# Sheet1.net
KiCad netlist of a schematic drawn in Altium Designer
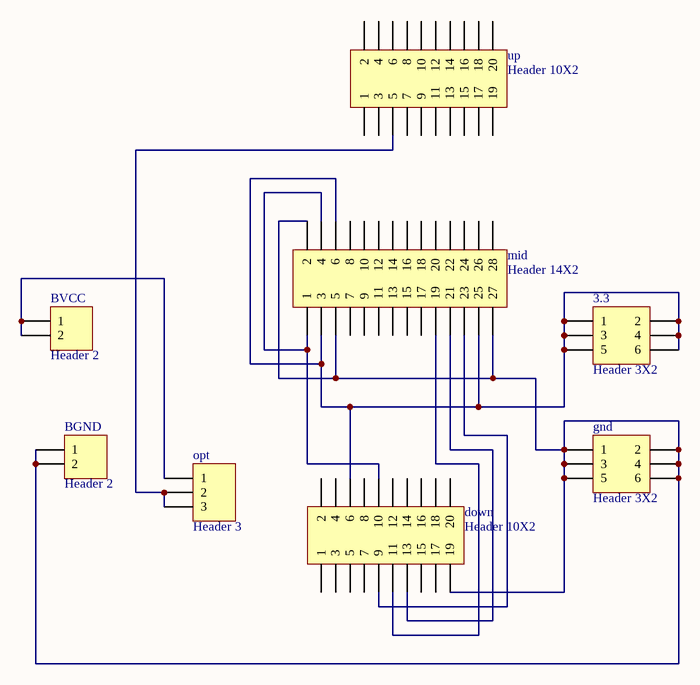
[diagram p0: Sheet1.SchDoc]

(export (version "E")
  (design (tool "Eeschema 10.0.6"))
  (components
    (comp (ref "3.3")
      (value "Header 3X2")
      (footprint "HDR2X3")
      (description "Header, 3-Pin, Dual row")
      (fields (field (name "PUBLISHER") "Altium Limited"))
      (libsource (lib "Miscellaneous Connectors") (part "Header 3X2"))
    )
    (comp (ref "BGND")
      (value "Header 2")
      (footprint "HDR1X2")
      (description "Header, 2-Pin")
      (fields (field (name "PUBLISHER") "Altium Limited"))
      (libsource (lib "Miscellaneous Connectors") (part "Header 2"))
    )
    (comp (ref "BVCC")
      (value "Header 2")
      (footprint "HDR1X2")
      (description "Header, 2-Pin")
      (fields (field (name "PUBLISHER") "Altium Limited"))
      (libsource (lib "Miscellaneous Connectors") (part "Header 2"))
    )
    (comp (ref "down")
      (value "Header 10X2")
      (footprint "HDR2X10")
      (description "Header, 10-Pin, Dual row")
      (fields (field (name "PUBLISHER") "Altium Limited"))
      (libsource (lib "Miscellaneous Connectors") (part "Header 10X2"))
    )
    (comp (ref "gnd")
      (value "Header 3X2")
      (footprint "HDR2X3")
      (description "Header, 3-Pin, Dual row")
      (fields (field (name "PUBLISHER") "Altium Limited"))
      (libsource (lib "Miscellaneous Connectors") (part "Header 3X2"))
    )
    (comp (ref "mid")
      (value "Header 14X2")
      (footprint "HDR2X14")
      (description "Header, 14-Pin, Dual row")
      (fields (field (name "PUBLISHER") "Altium Limited"))
      (libsource (lib "Miscellaneous Connectors") (part "Header 14X2"))
    )
    (comp (ref "opt")
      (value "Header 3")
      (footprint "HDR1X3")
      (description "Header, 3-Pin")
      (fields (field (name "PUBLISHER") "Altium Limited"))
      (libsource (lib "Miscellaneous Connectors") (part "Header 3"))
    )
    (comp (ref "up")
      (value "Header 10X2")
      (footprint "HDR2X10")
      (description "Header, 10-Pin, Dual row")
      (fields (field (name "PUBLISHER") "Altium Limited"))
      (libsource (lib "Miscellaneous Connectors") (part "Header 10X2"))
    )
  )
  (nets
    (net (code "1") (name "Net-(3.3-Pad1)") (class "Default")
      (node (ref "3.3") (pin "1") (pinfunction "1_1") (pintype "passive"))
      (node (ref "3.3") (pin "2") (pinfunction "2_2") (pintype "passive"))
      (node (ref "3.3") (pin "3") (pinfunction "3_3") (pintype "passive"))
      (node (ref "3.3") (pin "4") (pinfunction "4_4") (pintype "passive"))
      (node (ref "3.3") (pin "5") (pinfunction "5_5") (pintype "passive"))
      (node (ref "3.3") (pin "6") (pinfunction "6_6") (pintype "passive"))
      (node (ref "down") (pin "6") (pinfunction "6_6") (pintype "passive"))
      (node (ref "mid") (pin "25") (pinfunction "25_25") (pintype "passive"))
      (node (ref "mid") (pin "3") (pinfunction "3_3") (pintype "passive"))
      (node (ref "mid") (pin "6") (pinfunction "6_6") (pintype "passive"))
    )
    (net (code "2") (name "Net-(BGND-Pad1)") (class "Default")
      (node (ref "BGND") (pin "1") (pinfunction "1_1") (pintype "passive"))
      (node (ref "BGND") (pin "2") (pinfunction "2_2") (pintype "passive"))
      (node (ref "down") (pin "19") (pinfunction "19_19") (pintype "passive"))
      (node (ref "gnd") (pin "1") (pinfunction "1_1") (pintype "passive"))
      (node (ref "gnd") (pin "2") (pinfunction "2_2") (pintype "passive"))
      (node (ref "gnd") (pin "3") (pinfunction "3_3") (pintype "passive"))
      (node (ref "gnd") (pin "4") (pinfunction "4_4") (pintype "passive"))
      (node (ref "gnd") (pin "5") (pinfunction "5_5") (pintype "passive"))
      (node (ref "gnd") (pin "6") (pinfunction "6_6") (pintype "passive"))
      (node (ref "mid") (pin "2") (pinfunction "2_2") (pintype "passive"))
      (node (ref "mid") (pin "27") (pinfunction "27_27") (pintype "passive"))
      (node (ref "mid") (pin "5") (pinfunction "5_5") (pintype "passive"))
    )
    (net (code "3") (name "Net-(BVCC-Pad1)") (class "Default")
      (node (ref "BVCC") (pin "1") (pinfunction "1_1") (pintype "passive"))
      (node (ref "BVCC") (pin "2") (pinfunction "2_2") (pintype "passive"))
      (node (ref "opt") (pin "1") (pinfunction "1_1") (pintype "passive"))
    )
    (net (code "4") (name "Net-(down-Pad9)") (class "Default")
      (node (ref "down") (pin "9") (pinfunction "9_9") (pintype "passive"))
      (node (ref "mid") (pin "23") (pinfunction "23_23") (pintype "passive"))
    )
    (net (code "5") (name "Net-(down-Pad10)") (class "Default")
      (node (ref "down") (pin "10") (pinfunction "10_10") (pintype "passive"))
      (node (ref "mid") (pin "1") (pinfunction "1_1") (pintype "passive"))
      (node (ref "mid") (pin "4") (pinfunction "4_4") (pintype "passive"))
    )
    (net (code "6") (name "Net-(down-Pad11)") (class "Default")
      (node (ref "down") (pin "11") (pinfunction "11_11") (pintype "passive"))
      (node (ref "mid") (pin "19") (pinfunction "19_19") (pintype "passive"))
    )
    (net (code "7") (name "Net-(down-Pad13)") (class "Default")
      (node (ref "down") (pin "13") (pinfunction "13_13") (pintype "passive"))
      (node (ref "mid") (pin "21") (pinfunction "21_21") (pintype "passive"))
    )
    (net (code "8") (name "Net-(opt-Pad2)") (class "Default")
      (node (ref "opt") (pin "2") (pinfunction "2_2") (pintype "passive"))
      (node (ref "opt") (pin "3") (pinfunction "3_3") (pintype "passive"))
      (node (ref "up") (pin "5") (pinfunction "5_5") (pintype "passive"))
    )
    (net (code "9") (name "unconnected-(down-Pad1)") (class "Default")
      (node (ref "down") (pin "1") (pinfunction "1_1") (pintype "passive"))
    )
    (net (code "10") (name "unconnected-(down-Pad2)") (class "Default")
      (node (ref "down") (pin "2") (pinfunction "2_2") (pintype "passive"))
    )
    (net (code "11") (name "unconnected-(down-Pad3)") (class "Default")
      (node (ref "down") (pin "3") (pinfunction "3_3") (pintype "passive"))
    )
    (net (code "12") (name "unconnected-(down-Pad4)") (class "Default")
      (node (ref "down") (pin "4") (pinfunction "4_4") (pintype "passive"))
    )
    (net (code "13") (name "unconnected-(down-Pad5)") (class "Default")
      (node (ref "down") (pin "5") (pinfunction "5_5") (pintype "passive"))
    )
    (net (code "14") (name "unconnected-(down-Pad7)") (class "Default")
      (node (ref "down") (pin "7") (pinfunction "7_7") (pintype "passive"))
    )
    (net (code "15") (name "unconnected-(down-Pad8)") (class "Default")
      (node (ref "down") (pin "8") (pinfunction "8_8") (pintype "passive"))
    )
    (net (code "16") (name "unconnected-(down-Pad12)") (class "Default")
      (node (ref "down") (pin "12") (pinfunction "12_12") (pintype "passive"))
    )
    (net (code "17") (name "unconnected-(down-Pad14)") (class "Default")
      (node (ref "down") (pin "14") (pinfunction "14_14") (pintype "passive"))
    )
    (net (code "18") (name "unconnected-(down-Pad15)") (class "Default")
      (node (ref "down") (pin "15") (pinfunction "15_15") (pintype "passive"))
    )
    (net (code "19") (name "unconnected-(down-Pad16)") (class "Default")
      (node (ref "down") (pin "16") (pinfunction "16_16") (pintype "passive"))
    )
    (net (code "20") (name "unconnected-(down-Pad17)") (class "Default")
      (node (ref "down") (pin "17") (pinfunction "17_17") (pintype "passive"))
    )
    (net (code "21") (name "unconnected-(down-Pad18)") (class "Default")
      (node (ref "down") (pin "18") (pinfunction "18_18") (pintype "passive"))
    )
    (net (code "22") (name "unconnected-(down-Pad20)") (class "Default")
      (node (ref "down") (pin "20") (pinfunction "20_20") (pintype "passive"))
    )
    (net (code "23") (name "unconnected-(mid-Pad7)") (class "Default")
      (node (ref "mid") (pin "7") (pinfunction "7_7") (pintype "passive"))
    )
    (net (code "24") (name "unconnected-(mid-Pad8)") (class "Default")
      (node (ref "mid") (pin "8") (pinfunction "8_8") (pintype "passive"))
    )
    (net (code "25") (name "unconnected-(mid-Pad9)") (class "Default")
      (node (ref "mid") (pin "9") (pinfunction "9_9") (pintype "passive"))
    )
    (net (code "26") (name "unconnected-(mid-Pad10)") (class "Default")
      (node (ref "mid") (pin "10") (pinfunction "10_10") (pintype "passive"))
    )
    (net (code "27") (name "unconnected-(mid-Pad11)") (class "Default")
      (node (ref "mid") (pin "11") (pinfunction "11_11") (pintype "passive"))
    )
    (net (code "28") (name "unconnected-(mid-Pad12)") (class "Default")
      (node (ref "mid") (pin "12") (pinfunction "12_12") (pintype "passive"))
    )
    (net (code "29") (name "unconnected-(mid-Pad13)") (class "Default")
      (node (ref "mid") (pin "13") (pinfunction "13_13") (pintype "passive"))
    )
    (net (code "30") (name "unconnected-(mid-Pad14)") (class "Default")
      (node (ref "mid") (pin "14") (pinfunction "14_14") (pintype "passive"))
    )
    (net (code "31") (name "unconnected-(mid-Pad15)") (class "Default")
      (node (ref "mid") (pin "15") (pinfunction "15_15") (pintype "passive"))
    )
    (net (code "32") (name "unconnected-(mid-Pad16)") (class "Default")
      (node (ref "mid") (pin "16") (pinfunction "16_16") (pintype "passive"))
    )
    (net (code "33") (name "unconnected-(mid-Pad17)") (class "Default")
      (node (ref "mid") (pin "17") (pinfunction "17_17") (pintype "passive"))
    )
    (net (code "34") (name "unconnected-(mid-Pad18)") (class "Default")
      (node (ref "mid") (pin "18") (pinfunction "18_18") (pintype "passive"))
    )
    (net (code "35") (name "unconnected-(mid-Pad20)") (class "Default")
      (node (ref "mid") (pin "20") (pinfunction "20_20") (pintype "passive"))
    )
    (net (code "36") (name "unconnected-(mid-Pad22)") (class "Default")
      (node (ref "mid") (pin "22") (pinfunction "22_22") (pintype "passive"))
    )
    (net (code "37") (name "unconnected-(mid-Pad24)") (class "Default")
      (node (ref "mid") (pin "24") (pinfunction "24_24") (pintype "passive"))
    )
    (net (code "38") (name "unconnected-(mid-Pad26)") (class "Default")
      (node (ref "mid") (pin "26") (pinfunction "26_26") (pintype "passive"))
    )
    (net (code "39") (name "unconnected-(mid-Pad28)") (class "Default")
      (node (ref "mid") (pin "28") (pinfunction "28_28") (pintype "passive"))
    )
    (net (code "40") (name "unconnected-(up-Pad1)") (class "Default")
      (node (ref "up") (pin "1") (pinfunction "1_1") (pintype "passive"))
    )
    (net (code "41") (name "unconnected-(up-Pad2)") (class "Default")
      (node (ref "up") (pin "2") (pinfunction "2_2") (pintype "passive"))
    )
    (net (code "42") (name "unconnected-(up-Pad3)") (class "Default")
      (node (ref "up") (pin "3") (pinfunction "3_3") (pintype "passive"))
    )
    (net (code "43") (name "unconnected-(up-Pad4)") (class "Default")
      (node (ref "up") (pin "4") (pinfunction "4_4") (pintype "passive"))
    )
    (net (code "44") (name "unconnected-(up-Pad6)") (class "Default")
      (node (ref "up") (pin "6") (pinfunction "6_6") (pintype "passive"))
    )
    (net (code "45") (name "unconnected-(up-Pad7)") (class "Default")
      (node (ref "up") (pin "7") (pinfunction "7_7") (pintype "passive"))
    )
    (net (code "46") (name "unconnected-(up-Pad8)") (class "Default")
      (node (ref "up") (pin "8") (pinfunction "8_8") (pintype "passive"))
    )
    (net (code "47") (name "unconnected-(up-Pad9)") (class "Default")
      (node (ref "up") (pin "9") (pinfunction "9_9") (pintype "passive"))
    )
    (net (code "48") (name "unconnected-(up-Pad10)") (class "Default")
      (node (ref "up") (pin "10") (pinfunction "10_10") (pintype "passive"))
    )
    (net (code "49") (name "unconnected-(up-Pad11)") (class "Default")
      (node (ref "up") (pin "11") (pinfunction "11_11") (pintype "passive"))
    )
    (net (code "50") (name "unconnected-(up-Pad12)") (class "Default")
      (node (ref "up") (pin "12") (pinfunction "12_12") (pintype "passive"))
    )
    (net (code "51") (name "unconnected-(up-Pad13)") (class "Default")
      (node (ref "up") (pin "13") (pinfunction "13_13") (pintype "passive"))
    )
    (net (code "52") (name "unconnected-(up-Pad14)") (class "Default")
      (node (ref "up") (pin "14") (pinfunction "14_14") (pintype "passive"))
    )
    (net (code "53") (name "unconnected-(up-Pad15)") (class "Default")
      (node (ref "up") (pin "15") (pinfunction "15_15") (pintype "passive"))
    )
    (net (code "54") (name "unconnected-(up-Pad16)") (class "Default")
      (node (ref "up") (pin "16") (pinfunction "16_16") (pintype "passive"))
    )
    (net (code "55") (name "unconnected-(up-Pad17)") (class "Default")
      (node (ref "up") (pin "17") (pinfunction "17_17") (pintype "passive"))
    )
    (net (code "56") (name "unconnected-(up-Pad18)") (class "Default")
      (node (ref "up") (pin "18") (pinfunction "18_18") (pintype "passive"))
    )
    (net (code "57") (name "unconnected-(up-Pad19)") (class "Default")
      (node (ref "up") (pin "19") (pinfunction "19_19") (pintype "passive"))
    )
    (net (code "58") (name "unconnected-(up-Pad20)") (class "Default")
      (node (ref "up") (pin "20") (pinfunction "20_20") (pintype "passive"))
    )
  )
)
